# 1-WireWeMos.net
KiCad netlist of a schematic drawn in EAGLE
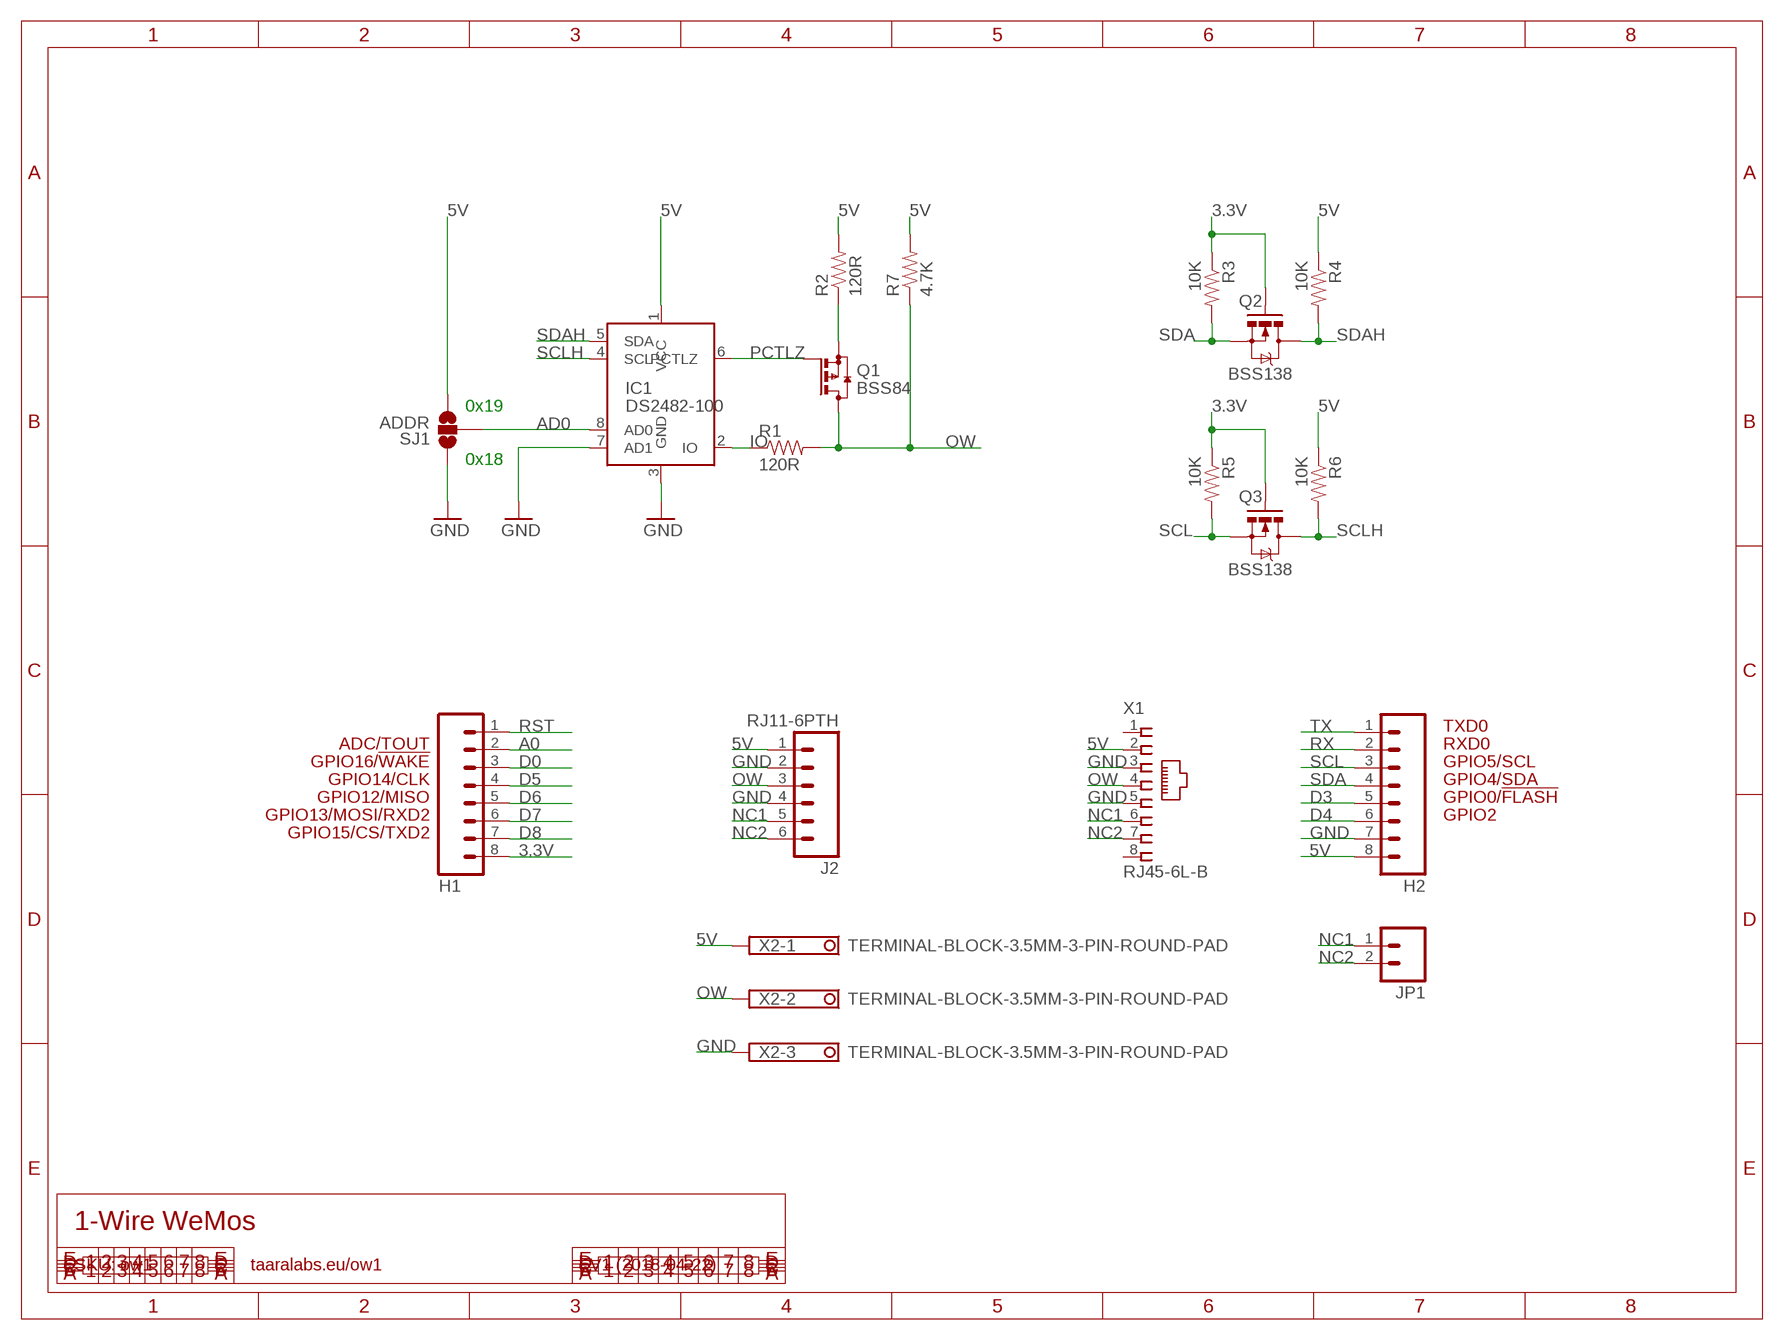
[diagram p0: schematic, sheet 1]

(export (version "E")
  (design (tool "Eeschema 10.0.6"))
  (components
    (comp (ref "H1")
      (value "M08")
      (footprint "eagle-import:1X08")
      (libsource (lib "eagle-import") (part "M08"))
    )
    (comp (ref "H2")
      (value "M08")
      (footprint "eagle-import:1X08")
      (libsource (lib "eagle-import") (part "M08"))
    )
    (comp (ref "IC1")
      (value "DS2482-100")
      (footprint "eagle-import:SO08")
      (libsource (lib "eagle-import") (part "DS2482-100"))
    )
    (comp (ref "J2")
      (value "RJ11-6PTH")
      (footprint "eagle-import:RJ11-6")
      (libsource (lib "eagle-import") (part "RJ11-6PTH"))
    )
    (comp (ref "JP1")
      (value "M02PTH")
      (footprint "eagle-import:1X02")
      (libsource (lib "eagle-import") (part "M02PTH"))
    )
    (comp (ref "Q1")
      (value "BSS84")
      (footprint "eagle-import:SOT23")
      (libsource (lib "eagle-import") (part "BSS84"))
    )
    (comp (ref "Q2")
      (value "BSS138")
      (footprint "eagle-import:SOT23-3")
      (libsource (lib "eagle-import") (part "MOSFET-NCHANNELSMD"))
    )
    (comp (ref "Q3")
      (value "BSS138")
      (footprint "eagle-import:SOT23-3")
      (libsource (lib "eagle-import") (part "MOSFET-NCHANNELSMD"))
    )
    (comp (ref "R1")
      (value "120R")
      (footprint "eagle-import:0603-RES")
      (libsource (lib "eagle-import") (part "RESISTOR0603-RES"))
    )
    (comp (ref "R2")
      (value "120R")
      (footprint "eagle-import:0603-RES")
      (libsource (lib "eagle-import") (part "RESISTOR0603-RES"))
    )
    (comp (ref "R3")
      (value "10K")
      (footprint "eagle-import:0603-RES")
      (libsource (lib "eagle-import") (part "RESISTOR0603-RES"))
    )
    (comp (ref "R4")
      (value "10K")
      (footprint "eagle-import:0603-RES")
      (libsource (lib "eagle-import") (part "RESISTOR0603-RES"))
    )
    (comp (ref "R5")
      (value "10K")
      (footprint "eagle-import:0603-RES")
      (libsource (lib "eagle-import") (part "RESISTOR0603-RES"))
    )
    (comp (ref "R6")
      (value "10K")
      (footprint "eagle-import:0603-RES")
      (libsource (lib "eagle-import") (part "RESISTOR0603-RES"))
    )
    (comp (ref "R7")
      (value "4.7K")
      (footprint "eagle-import:0603-RES")
      (libsource (lib "eagle-import") (part "RESISTOR0603-RES"))
    )
    (comp (ref "SJ1")
      (value "ADDR")
      (footprint "eagle-import:SJ_3_PASTE1&2")
      (libsource (lib "eagle-import") (part "SOLDERJUMPER_2WAYPASTE1&2"))
    )
    (comp (ref "X1")
      (value "RJ45-6L-B")
      (footprint "eagle-import:RJ45-NO-SHIELD")
      (libsource (lib "eagle-import") (part "RJ45-6L-B"))
    )
    (comp (ref "X2")
      (value "TERMINAL-BLOCK-3.5MM-3-PIN-ROUND-PAD")
      (footprint "eagle-import:TERMINAL-BLOCK-3-PIN-3.5MM-ROUND-PAD")
      (libsource (lib "eagle-import") (part "TERMINAL-BLOCK-3.5MM-3-PIN-ROUND-PAD"))
    )
  )
  (nets
    (net (code "1") (name "/3.3V") (class "Default")
      (node (ref "H1") (pin "8") (pinfunction "8_8") (pintype "passive"))
      (node (ref "Q2") (pin "1") (pinfunction "G_1") (pintype "passive"))
      (node (ref "Q3") (pin "1") (pinfunction "G_1") (pintype "passive"))
      (node (ref "R3") (pin "1") (pinfunction "1_1") (pintype "passive"))
      (node (ref "R5") (pin "1") (pinfunction "1_1") (pintype "passive"))
    )
    (net (code "2") (name "/5V") (class "Default")
      (node (ref "H2") (pin "8") (pinfunction "8_8") (pintype "passive"))
      (node (ref "IC1") (pin "1") (pinfunction "VCC_1") (pintype "power_in"))
      (node (ref "J2") (pin "1") (pinfunction "1_1") (pintype "passive"))
      (node (ref "R2") (pin "2") (pinfunction "2_2") (pintype "passive"))
      (node (ref "R4") (pin "1") (pinfunction "1_1") (pintype "passive"))
      (node (ref "R6") (pin "1") (pinfunction "1_1") (pintype "passive"))
      (node (ref "R7") (pin "2") (pinfunction "2_2") (pintype "passive"))
      (node (ref "SJ1") (pin "3") (pinfunction "3_3") (pintype "passive"))
      (node (ref "X1") (pin "2") (pinfunction "2_2") (pintype "passive"))
      (node (ref "X2") (pin "1") (pinfunction "K_1") (pintype "passive"))
    )
    (net (code "3") (name "/A0") (class "Default")
      (node (ref "H1") (pin "2") (pinfunction "2_2") (pintype "passive"))
    )
    (net (code "4") (name "/AD0") (class "Default")
      (node (ref "IC1") (pin "8") (pinfunction "AD0_8") (pintype "input"))
      (node (ref "SJ1") (pin "2") (pinfunction "2_2") (pintype "passive"))
    )
    (net (code "5") (name "/D0") (class "Default")
      (node (ref "H1") (pin "3") (pinfunction "3_3") (pintype "passive"))
    )
    (net (code "6") (name "/D3") (class "Default")
      (node (ref "H2") (pin "5") (pinfunction "5_5") (pintype "passive"))
    )
    (net (code "7") (name "/D4") (class "Default")
      (node (ref "H2") (pin "6") (pinfunction "6_6") (pintype "passive"))
    )
    (net (code "8") (name "/D5") (class "Default")
      (node (ref "H1") (pin "4") (pinfunction "4_4") (pintype "passive"))
    )
    (net (code "9") (name "/D6") (class "Default")
      (node (ref "H1") (pin "5") (pinfunction "5_5") (pintype "passive"))
    )
    (net (code "10") (name "/D7") (class "Default")
      (node (ref "H1") (pin "6") (pinfunction "6_6") (pintype "passive"))
    )
    (net (code "11") (name "/D8") (class "Default")
      (node (ref "H1") (pin "7") (pinfunction "7_7") (pintype "passive"))
    )
    (net (code "12") (name "/IO") (class "Default")
      (node (ref "IC1") (pin "2") (pinfunction "IO_2") (pintype "bidirectional"))
      (node (ref "R1") (pin "1") (pinfunction "1_1") (pintype "passive"))
    )
    (net (code "13") (name "/NC1") (class "Default")
      (node (ref "J2") (pin "5") (pinfunction "5_5") (pintype "passive"))
      (node (ref "JP1") (pin "1") (pinfunction "1_1") (pintype "passive"))
      (node (ref "X1") (pin "6") (pinfunction "6_6") (pintype "passive"))
    )
    (net (code "14") (name "/NC2") (class "Default")
      (node (ref "J2") (pin "6") (pinfunction "6_6") (pintype "passive"))
      (node (ref "JP1") (pin "2") (pinfunction "2_2") (pintype "passive"))
      (node (ref "X1") (pin "7") (pinfunction "7_7") (pintype "passive"))
    )
    (net (code "15") (name "/OW") (class "Default")
      (node (ref "J2") (pin "3") (pinfunction "3_3") (pintype "passive"))
      (node (ref "Q1") (pin "3") (pinfunction "D_3") (pintype "passive"))
      (node (ref "R1") (pin "2") (pinfunction "2_2") (pintype "passive"))
      (node (ref "R7") (pin "1") (pinfunction "1_1") (pintype "passive"))
      (node (ref "X1") (pin "4") (pinfunction "4_4") (pintype "passive"))
      (node (ref "X2") (pin "2") (pinfunction "K_2") (pintype "passive"))
    )
    (net (code "16") (name "/PCTLZ") (class "Default")
      (node (ref "IC1") (pin "6") (pinfunction "PCTLZ_6") (pintype "output"))
      (node (ref "Q1") (pin "1") (pinfunction "G_1") (pintype "passive"))
    )
    (net (code "17") (name "/RST") (class "Default")
      (node (ref "H1") (pin "1") (pinfunction "1_1") (pintype "passive"))
    )
    (net (code "18") (name "/RX") (class "Default")
      (node (ref "H2") (pin "2") (pinfunction "2_2") (pintype "passive"))
    )
    (net (code "19") (name "/SCL") (class "Default")
      (node (ref "H2") (pin "3") (pinfunction "3_3") (pintype "passive"))
      (node (ref "Q3") (pin "2") (pinfunction "S_2") (pintype "passive"))
      (node (ref "R5") (pin "2") (pinfunction "2_2") (pintype "passive"))
    )
    (net (code "20") (name "/SCLH") (class "Default")
      (node (ref "IC1") (pin "4") (pinfunction "SCL_4") (pintype "bidirectional"))
      (node (ref "Q3") (pin "3") (pinfunction "D_3") (pintype "passive"))
      (node (ref "R6") (pin "2") (pinfunction "2_2") (pintype "passive"))
    )
    (net (code "21") (name "/SDA") (class "Default")
      (node (ref "H2") (pin "4") (pinfunction "4_4") (pintype "passive"))
      (node (ref "Q2") (pin "2") (pinfunction "S_2") (pintype "passive"))
      (node (ref "R3") (pin "2") (pinfunction "2_2") (pintype "passive"))
    )
    (net (code "22") (name "/SDAH") (class "Default")
      (node (ref "IC1") (pin "5") (pinfunction "SDA_5") (pintype "bidirectional"))
      (node (ref "Q2") (pin "3") (pinfunction "D_3") (pintype "passive"))
      (node (ref "R4") (pin "2") (pinfunction "2_2") (pintype "passive"))
    )
    (net (code "23") (name "/TX") (class "Default")
      (node (ref "H2") (pin "1") (pinfunction "1_1") (pintype "passive"))
    )
    (net (code "24") (name "GND") (class "Default")
      (node (ref "H2") (pin "7") (pinfunction "7_7") (pintype "passive"))
      (node (ref "IC1") (pin "3") (pinfunction "GND_3") (pintype "power_in"))
      (node (ref "IC1") (pin "7") (pinfunction "AD1_7") (pintype "input"))
      (node (ref "J2") (pin "2") (pinfunction "2_2") (pintype "passive"))
      (node (ref "J2") (pin "4") (pinfunction "4_4") (pintype "passive"))
      (node (ref "SJ1") (pin "1") (pinfunction "1_1") (pintype "passive"))
      (node (ref "X1") (pin "3") (pinfunction "3_3") (pintype "passive"))
      (node (ref "X1") (pin "5") (pinfunction "5_5") (pintype "passive"))
      (node (ref "X2") (pin "3") (pinfunction "K_3") (pintype "passive"))
    )
    (net (code "25") (name "Net-(Q1-S)") (class "Default")
      (node (ref "Q1") (pin "2") (pinfunction "S_2") (pintype "passive"))
      (node (ref "R2") (pin "1") (pinfunction "1_1") (pintype "passive"))
    )
    (net (code "26") (name "unconnected-(X1-Pad1)") (class "Default")
      (node (ref "X1") (pin "1") (pinfunction "1_1") (pintype "passive"))
    )
    (net (code "27") (name "unconnected-(X1-Pad8)") (class "Default")
      (node (ref "X1") (pin "8") (pinfunction "8_8") (pintype "passive"))
    )
  )
)
